# sliding_protentiometer.net
KiCad netlist of a schematic drawn in EAGLE
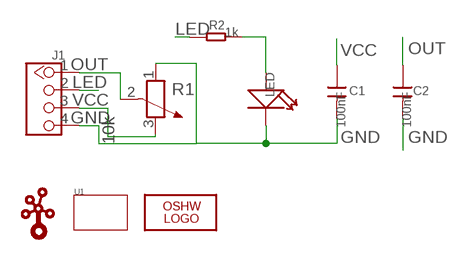
[diagram p0: schematic, sheet 1]

(export (version "E")
  (design (tool "Eeschema 10.0.6"))
  (components
    (comp (ref "C1")
      (value "100nF")
      (footprint "eagle-import:0805")
      (libsource (lib "eagle-import") (part "C-0805"))
    )
    (comp (ref "C2")
      (value "100nF")
      (footprint "eagle-import:0805")
      (libsource (lib "eagle-import") (part "C-0805"))
    )
    (comp (ref "J1")
      (value "TWIG-4P-2.0-2.0")
      (footprint "eagle-import:4P-2.0")
      (libsource (lib "eagle-import") (part "TWIG-4P-2.0-2.0"))
    )
    (comp (ref "LED")
      (value "LED'0805'")
      (footprint "eagle-import:LED-0805")
      (libsource (lib "eagle-import") (part "LED'0805'"))
    )
    (comp (ref "LOGO1")
      (value "LOGO-OSHW-FILLX0200-NT")
      (footprint "eagle-import:OSHW_FILLX200_NOTEXT")
      (libsource (lib "eagle-import") (part "LOGO-OSHW-FILLX0200-NT"))
    )
    (comp (ref "R1")
      (value "10k")
      (footprint "eagle-import:3P-SQUA-45.6X10X5.8H")
      (libsource (lib "eagle-import") (part "R-POTENTIOMETER"))
    )
    (comp (ref "R2")
      (value "1k")
      (footprint "eagle-import:0805")
      (libsource (lib "eagle-import") (part "R-0805"))
    )
    (comp (ref "U$1")
      (value "LOGO-TWIG")
      (footprint "eagle-import:TWIGLOGO")
      (libsource (lib "eagle-import") (part "LOGO-TWIG"))
    )
    (comp (ref "U1")
      (value "TWIG'3U'")
      (footprint "eagle-import:3U-DIM-W_-DRILL")
      (libsource (lib "eagle-import") (part "TWIG'3U'"))
    )
  )
  (nets
    (net (code "1") (name "/GND") (class "Default")
      (node (ref "C1") (pin "2") (pinfunction "2_2") (pintype "passive"))
      (node (ref "C2") (pin "2") (pinfunction "2_2") (pintype "passive"))
      (node (ref "J1") (pin "4") (pinfunction "4_4") (pintype "bidirectional"))
      (node (ref "LED") (pin "-") (pinfunction "-_-") (pintype "passive"))
      (node (ref "R1") (pin "1") (pinfunction "1_1") (pintype "passive"))
    )
    (net (code "2") (name "/LED") (class "Default")
      (node (ref "J1") (pin "2") (pinfunction "2_2") (pintype "bidirectional"))
      (node (ref "R2") (pin "1") (pinfunction "1_1") (pintype "passive"))
    )
    (net (code "3") (name "/OUT") (class "Default")
      (node (ref "C2") (pin "1") (pinfunction "1_1") (pintype "passive"))
      (node (ref "J1") (pin "1") (pinfunction "1_1") (pintype "bidirectional"))
      (node (ref "R1") (pin "2") (pinfunction "3_2") (pintype "passive"))
    )
    (net (code "4") (name "/VCC") (class "Default")
      (node (ref "C1") (pin "1") (pinfunction "1_1") (pintype "passive"))
      (node (ref "J1") (pin "3") (pinfunction "3_3") (pintype "bidirectional"))
      (node (ref "R1") (pin "3") (pinfunction "2_3") (pintype "passive"))
    )
    (net (code "5") (name "Net-(LED-Pad+)") (class "Default")
      (node (ref "LED") (pin "+") (pinfunction "+_+") (pintype "passive"))
      (node (ref "R2") (pin "2") (pinfunction "2_2") (pintype "passive"))
    )
  )
)
